# Sheet2.net
KiCad netlist of a schematic drawn in Altium Designer
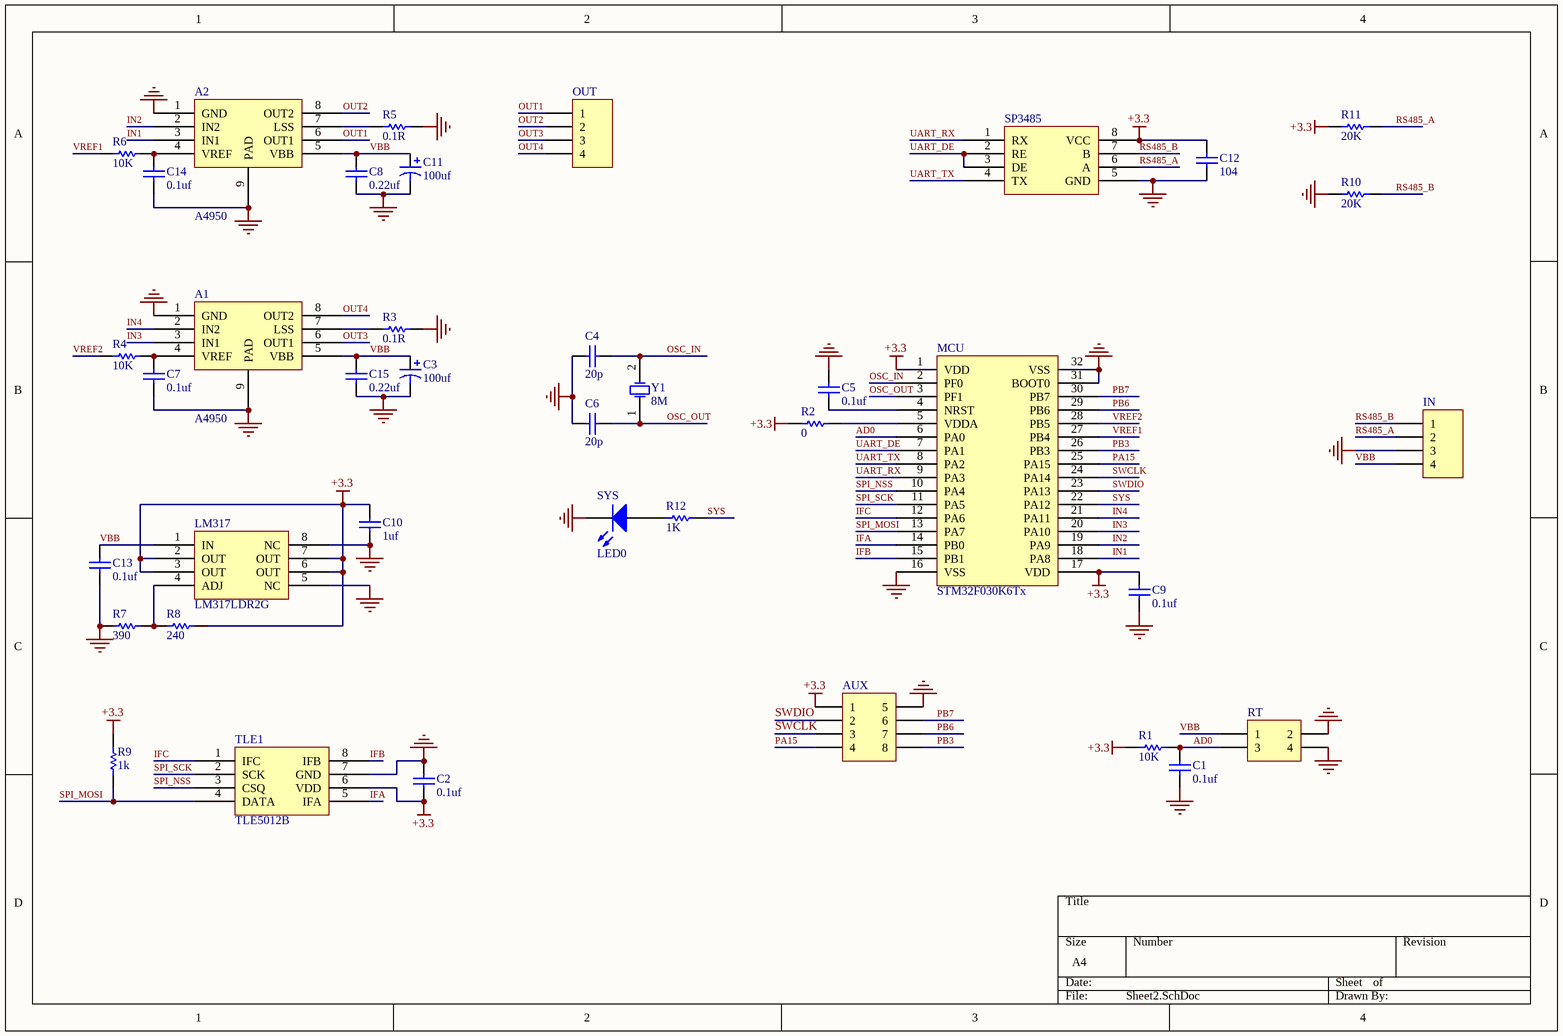
[diagram p0: Sheet2.SchDoc]

(export (version "E")
  (design (tool "Eeschema 10.0.6"))
  (components
    (comp (ref "A1") (value "A4950") (footprint "SOIC-8P") (libsource (lib "Schlib1") (part "A4950")))
    (comp (ref "A2") (value "A4950") (footprint "SOIC-8P") (libsource (lib "Schlib1") (part "A4950")))
    (comp (ref "AUX")
      (value "Header 4X2A")
      (footprint "HDR2X4")
      (description "Header, 4-Pin, Dual row")
      (fields (field (name "PUBLISHER") "Altium Limited"))
      (libsource (lib "Miscellaneous Connectors") (part "Header 4X2A"))
    )
    (comp (ref "C1")
      (value "0.1uf")
      (footprint "0603")
      (description "Capacitor")
      (fields (field (name "Comment") "Cap") (field (name "PUBLISHER") "Altium Limited"))
      (libsource (lib "Miscellaneous Devices") (part "Cap"))
    )
    (comp (ref "C2")
      (value "0.1uf")
      (footprint "0603")
      (description "Capacitor")
      (fields (field (name "Comment") "Cap") (field (name "PUBLISHER") "Altium Limited"))
      (libsource (lib "Miscellaneous Devices") (part "Cap"))
    )
    (comp (ref "C3")
      (value "100uf")
      (footprint "RB.1/.2-F")
      (description "Polarized Capacitor (Radial)")
      (fields (field (name "Comment") "Cap Pol1") (field (name "PUBLISHER") "Altium Limited"))
      (libsource (lib "Miscellaneous Devices") (part "Cap Pol1"))
    )
    (comp (ref "C4")
      (value "20p")
      (footprint "0603")
      (description "Capacitor")
      (fields (field (name "Comment") "Cap") (field (name "PUBLISHER") "Altium Limited"))
      (libsource (lib "Miscellaneous Devices") (part "Cap"))
    )
    (comp (ref "C5")
      (value "0.1uf")
      (footprint "0603")
      (description "Capacitor")
      (fields (field (name "Comment") "Cap") (field (name "PUBLISHER") "Altium Limited"))
      (libsource (lib "Miscellaneous Devices") (part "Cap"))
    )
    (comp (ref "C6")
      (value "20p")
      (footprint "0603")
      (description "Capacitor")
      (fields (field (name "Comment") "Cap") (field (name "PUBLISHER") "Altium Limited"))
      (libsource (lib "Miscellaneous Devices") (part "Cap"))
    )
    (comp (ref "C7")
      (value "0.1uf")
      (footprint "0603")
      (description "Capacitor")
      (fields (field (name "Comment") "Cap") (field (name "PUBLISHER") "Altium Limited"))
      (libsource (lib "Miscellaneous Devices") (part "Cap"))
    )
    (comp (ref "C8")
      (value "0.22uf")
      (footprint "0603")
      (description "Capacitor")
      (fields (field (name "Comment") "Cap") (field (name "PUBLISHER") "Altium Limited"))
      (libsource (lib "Miscellaneous Devices") (part "Cap"))
    )
    (comp (ref "C9")
      (value "0.1uf")
      (footprint "0603")
      (description "Capacitor")
      (fields (field (name "Comment") "Cap") (field (name "PUBLISHER") "Altium Limited"))
      (libsource (lib "Miscellaneous Devices") (part "Cap"))
    )
    (comp (ref "C10")
      (value "1uf")
      (footprint "0603")
      (description "Capacitor")
      (fields (field (name "Comment") "Cap") (field (name "PUBLISHER") "Altium Limited"))
      (libsource (lib "Miscellaneous Devices") (part "Cap"))
    )
    (comp (ref "C11")
      (value "100uf")
      (footprint "RB.1/.2-F")
      (description "Polarized Capacitor (Radial)")
      (fields (field (name "Comment") "Cap Pol1") (field (name "PUBLISHER") "Altium Limited"))
      (libsource (lib "Miscellaneous Devices") (part "Cap Pol1"))
    )
    (comp (ref "C12")
      (value "104")
      (footprint "0603")
      (description "Capacitor")
      (fields (field (name "Comment") "Cap") (field (name "PUBLISHER") "Altium Limited"))
      (libsource (lib "Miscellaneous Devices") (part "Cap"))
    )
    (comp (ref "C13")
      (value "0.1uf")
      (footprint "0603")
      (description "Capacitor")
      (fields (field (name "Comment") "Cap") (field (name "PUBLISHER") "Altium Limited"))
      (libsource (lib "Miscellaneous Devices") (part "Cap"))
    )
    (comp (ref "C14")
      (value "0.1uf")
      (footprint "0603")
      (description "Capacitor")
      (fields (field (name "Comment") "Cap") (field (name "PUBLISHER") "Altium Limited"))
      (libsource (lib "Miscellaneous Devices") (part "Cap"))
    )
    (comp (ref "C15")
      (value "0.22uf")
      (footprint "0603")
      (description "Capacitor")
      (fields (field (name "Comment") "Cap") (field (name "PUBLISHER") "Altium Limited"))
      (libsource (lib "Miscellaneous Devices") (part "Cap"))
    )
    (comp (ref "IN")
      (value "Header 4")
      (footprint "KF2EDG3.81-4P")
      (description "Header, 4-Pin")
      (fields (field (name "PUBLISHER") "Altium Limited"))
      (libsource (lib "Miscellaneous Connectors") (part "Header 4"))
    )
    (comp (ref "LM317")
      (value "LM317LDR2G")
      (footprint "SOIC-8")
      (libsource (lib "Schlib1") (part "LM317LDR2G"))
    )
    (comp (ref "MCU")
      (value "STM32F030K6Tx")
      (footprint "LQFP-32")
      (libsource (lib "Schlib1") (part "STM32F030K6Tx"))
    )
    (comp (ref "OUT")
      (value "Header 4")
      (footprint "HDR4X1-2.54-R")
      (description "Header, 4-Pin")
      (fields (field (name "PUBLISHER") "Altium Limited"))
      (libsource (lib "Miscellaneous Connectors") (part "Header 4"))
    )
    (comp (ref "R1")
      (value "10K")
      (footprint "0603")
      (description "Resistor")
      (fields (field (name "Comment") "Res1") (field (name "PUBLISHER") "Altium Limited"))
      (libsource (lib "Miscellaneous Devices") (part "Res1"))
    )
    (comp (ref "R2")
      (value "0")
      (footprint "0603")
      (description "Resistor")
      (fields (field (name "Comment") "Res1") (field (name "PUBLISHER") "Altium Limited"))
      (libsource (lib "Miscellaneous Devices") (part "Res1"))
    )
    (comp (ref "R3")
      (value "0.1R")
      (footprint "1206")
      (description "Resistor")
      (fields (field (name "Comment") "Res1") (field (name "PUBLISHER") "Altium Limited"))
      (libsource (lib "Miscellaneous Devices") (part "Res1"))
    )
    (comp (ref "R4")
      (value "10K")
      (footprint "0603")
      (description "Resistor")
      (fields (field (name "Comment") "Res1") (field (name "PUBLISHER") "Altium Limited"))
      (libsource (lib "Miscellaneous Devices") (part "Res1"))
    )
    (comp (ref "R5")
      (value "0.1R")
      (footprint "1206")
      (description "Resistor")
      (fields (field (name "Comment") "Res1") (field (name "PUBLISHER") "Altium Limited"))
      (libsource (lib "Miscellaneous Devices") (part "Res1"))
    )
    (comp (ref "R6")
      (value "10K")
      (footprint "0603")
      (description "Resistor")
      (fields (field (name "Comment") "Res1") (field (name "PUBLISHER") "Altium Limited"))
      (libsource (lib "Miscellaneous Devices") (part "Res1"))
    )
    (comp (ref "R7")
      (value "390")
      (footprint "0603")
      (description "Resistor")
      (fields (field (name "Comment") "Res1") (field (name "PUBLISHER") "Altium Limited"))
      (libsource (lib "Miscellaneous Devices") (part "Res1"))
    )
    (comp (ref "R8")
      (value "240")
      (footprint "0603")
      (description "Resistor")
      (fields (field (name "Comment") "Res1") (field (name "PUBLISHER") "Altium Limited"))
      (libsource (lib "Miscellaneous Devices") (part "Res1"))
    )
    (comp (ref "R9")
      (value "1k")
      (footprint "0603")
      (description "Resistor")
      (fields (field (name "Comment") "Res1") (field (name "PUBLISHER") "Altium Limited"))
      (libsource (lib "Miscellaneous Devices") (part "Res1"))
    )
    (comp (ref "R10")
      (value "20K")
      (footprint "0603")
      (description "Resistor")
      (fields (field (name "Comment") "Res1") (field (name "PUBLISHER") "Altium Limited"))
      (libsource (lib "Miscellaneous Devices") (part "Res1"))
    )
    (comp (ref "R11")
      (value "20K")
      (footprint "0603")
      (description "Resistor")
      (fields (field (name "Comment") "Res1") (field (name "PUBLISHER") "Altium Limited"))
      (libsource (lib "Miscellaneous Devices") (part "Res1"))
    )
    (comp (ref "R12")
      (value "1K")
      (footprint "0603")
      (description "Resistor")
      (fields (field (name "Comment") "Res1") (field (name "PUBLISHER") "Altium Limited"))
      (libsource (lib "Miscellaneous Devices") (part "Res1"))
    )
    (comp (ref "RT")
      (value "Header 2X2")
      (footprint "HDR2X2")
      (description "Header, 2-Pin, Dual row")
      (fields (field (name "PUBLISHER") "Altium Limited"))
      (libsource (lib "Miscellaneous Connectors") (part "Header 2X2"))
    )
    (comp (ref "SP3485") (value "SP3485") (footprint "SOIC-8") (libsource (lib "Schlib1") (part "SP3485")))
    (comp (ref "SYS")
      (value "LED0")
      (footprint "0603")
      (description "Typical INFRARED GaAs LED")
      (fields (field (name "PUBLISHER") "Altium Limited"))
      (libsource (lib "Miscellaneous Devices") (part "LED0"))
    )
    (comp (ref "TLE1") (value "TLE5012B") (footprint "SOIC-8") (libsource (lib "Schlib1") (part "TLE5012B")))
    (comp (ref "Y1")
      (value "8M")
      (footprint "XTAL-1")
      (description "Crystal Oscillator")
      (fields (field (name "PUBLISHER") "Altium Limited"))
      (libsource (lib "Miscellaneous Devices") (part "XTAL"))
    )
  )
  (nets
    (net (code "1") (name "+3.3") (class "Default")
      (node (ref "AUX") (pin "1") (pinfunction "1_1") (pintype "passive"))
      (node (ref "C10") (pin "2") (pinfunction "2_2") (pintype "passive"))
      (node (ref "C12") (pin "2") (pinfunction "2_2") (pintype "passive"))
      (node (ref "C2") (pin "1") (pinfunction "1_1") (pintype "passive"))
      (node (ref "C9") (pin "2") (pinfunction "2_2") (pintype "passive"))
      (node (ref "LM317") (pin "2") (pinfunction "OUT_2") (pintype "passive"))
      (node (ref "LM317") (pin "3") (pinfunction "OUT_3") (pintype "passive"))
      (node (ref "LM317") (pin "6") (pinfunction "OUT_6") (pintype "passive"))
      (node (ref "LM317") (pin "7") (pinfunction "OUT_7") (pintype "passive"))
      (node (ref "MCU") (pin "1") (pinfunction "VDD_1") (pintype "passive"))
      (node (ref "MCU") (pin "17") (pinfunction "VDD_17") (pintype "passive"))
      (node (ref "R1") (pin "1") (pinfunction "1_1") (pintype "passive"))
      (node (ref "R11") (pin "1") (pinfunction "1_1") (pintype "passive"))
      (node (ref "R2") (pin "2") (pinfunction "2_2") (pintype "passive"))
      (node (ref "R8") (pin "1") (pinfunction "1_1") (pintype "passive"))
      (node (ref "R9") (pin "1") (pinfunction "1_1") (pintype "passive"))
      (node (ref "SP3485") (pin "8") (pinfunction "VCC_8") (pintype "passive"))
      (node (ref "TLE1") (pin "6") (pinfunction "VDD_6") (pintype "passive"))
    )
    (net (code "2") (name "/AD0") (class "Default")
      (node (ref "C1") (pin "1") (pinfunction "1_1") (pintype "passive"))
      (node (ref "MCU") (pin "6") (pinfunction "PA0_6") (pintype "passive"))
      (node (ref "R1") (pin "2") (pinfunction "2_2") (pintype "passive"))
      (node (ref "RT") (pin "3") (pinfunction "3_3") (pintype "passive"))
    )
    (net (code "3") (name "/IFA") (class "Default")
      (node (ref "MCU") (pin "14") (pinfunction "PB0_14") (pintype "passive"))
      (node (ref "TLE1") (pin "5") (pinfunction "IFA_5") (pintype "passive"))
    )
    (net (code "4") (name "/IFB") (class "Default")
      (node (ref "MCU") (pin "15") (pinfunction "PB1_15") (pintype "passive"))
      (node (ref "TLE1") (pin "8") (pinfunction "IFB_8") (pintype "passive"))
    )
    (net (code "5") (name "/IFC") (class "Default")
      (node (ref "MCU") (pin "12") (pinfunction "PA6_12") (pintype "passive"))
      (node (ref "TLE1") (pin "1") (pinfunction "IFC_1") (pintype "passive"))
    )
    (net (code "6") (name "/IN1") (class "Default")
      (node (ref "A2") (pin "3") (pinfunction "IN1_3") (pintype "passive"))
      (node (ref "MCU") (pin "18") (pinfunction "PA8_18") (pintype "passive"))
    )
    (net (code "7") (name "/IN2") (class "Default")
      (node (ref "A2") (pin "2") (pinfunction "IN2_2") (pintype "passive"))
      (node (ref "MCU") (pin "19") (pinfunction "PA9_19") (pintype "passive"))
    )
    (net (code "8") (name "/IN3") (class "Default")
      (node (ref "A1") (pin "3") (pinfunction "IN1_3") (pintype "passive"))
      (node (ref "MCU") (pin "20") (pinfunction "PA10_20") (pintype "passive"))
    )
    (net (code "9") (name "/IN4") (class "Default")
      (node (ref "A1") (pin "2") (pinfunction "IN2_2") (pintype "passive"))
      (node (ref "MCU") (pin "21") (pinfunction "PA11_21") (pintype "passive"))
    )
    (net (code "10") (name "/OSC_IN") (class "Default")
      (node (ref "C4") (pin "1") (pinfunction "1_1") (pintype "passive"))
      (node (ref "MCU") (pin "2") (pinfunction "PF0_2") (pintype "passive"))
      (node (ref "Y1") (pin "2") (pinfunction "OSC2_2") (pintype "passive"))
    )
    (net (code "11") (name "/OSC_OUT") (class "Default")
      (node (ref "C6") (pin "1") (pinfunction "1_1") (pintype "passive"))
      (node (ref "MCU") (pin "3") (pinfunction "PF1_3") (pintype "passive"))
      (node (ref "Y1") (pin "1") (pinfunction "OSC1_1") (pintype "passive"))
    )
    (net (code "12") (name "/OUT1") (class "Default")
      (node (ref "A2") (pin "6") (pinfunction "OUT1_6") (pintype "passive"))
      (node (ref "OUT") (pin "1") (pinfunction "1_1") (pintype "passive"))
    )
    (net (code "13") (name "/OUT2") (class "Default")
      (node (ref "A2") (pin "8") (pinfunction "OUT2_8") (pintype "passive"))
      (node (ref "OUT") (pin "2") (pinfunction "2_2") (pintype "passive"))
    )
    (net (code "14") (name "/OUT3") (class "Default")
      (node (ref "A1") (pin "6") (pinfunction "OUT1_6") (pintype "passive"))
      (node (ref "OUT") (pin "3") (pinfunction "3_3") (pintype "passive"))
    )
    (net (code "15") (name "/OUT4") (class "Default")
      (node (ref "A1") (pin "8") (pinfunction "OUT2_8") (pintype "passive"))
      (node (ref "OUT") (pin "4") (pinfunction "4_4") (pintype "passive"))
    )
    (net (code "16") (name "/PA15") (class "Default")
      (node (ref "AUX") (pin "4") (pinfunction "4_4") (pintype "passive"))
      (node (ref "MCU") (pin "25") (pinfunction "PA15_25") (pintype "passive"))
    )
    (net (code "17") (name "/PB3") (class "Default")
      (node (ref "AUX") (pin "8") (pinfunction "8_8") (pintype "passive"))
      (node (ref "MCU") (pin "26") (pinfunction "PB3_26") (pintype "passive"))
    )
    (net (code "18") (name "/PB6") (class "Default")
      (node (ref "AUX") (pin "7") (pinfunction "7_7") (pintype "passive"))
      (node (ref "MCU") (pin "29") (pinfunction "PB6_29") (pintype "passive"))
    )
    (net (code "19") (name "/PB7") (class "Default")
      (node (ref "AUX") (pin "6") (pinfunction "6_6") (pintype "passive"))
      (node (ref "MCU") (pin "30") (pinfunction "PB7_30") (pintype "passive"))
    )
    (net (code "20") (name "/RS485_A") (class "Default")
      (node (ref "IN") (pin "2") (pinfunction "2_2") (pintype "passive"))
      (node (ref "R11") (pin "2") (pinfunction "2_2") (pintype "passive"))
      (node (ref "SP3485") (pin "6") (pinfunction "A_6") (pintype "passive"))
    )
    (net (code "21") (name "/RS485_B") (class "Default")
      (node (ref "IN") (pin "1") (pinfunction "1_1") (pintype "passive"))
      (node (ref "R10") (pin "2") (pinfunction "2_2") (pintype "passive"))
      (node (ref "SP3485") (pin "7") (pinfunction "B_7") (pintype "passive"))
    )
    (net (code "22") (name "/SPI_MOSI") (class "Default")
      (node (ref "MCU") (pin "13") (pinfunction "PA7_13") (pintype "passive"))
      (node (ref "R9") (pin "2") (pinfunction "2_2") (pintype "passive"))
      (node (ref "TLE1") (pin "4") (pinfunction "DATA_4") (pintype "passive"))
    )
    (net (code "23") (name "/SPI_NSS") (class "Default")
      (node (ref "MCU") (pin "10") (pinfunction "PA4_10") (pintype "passive"))
      (node (ref "TLE1") (pin "3") (pinfunction "CSQ_3") (pintype "passive"))
    )
    (net (code "24") (name "/SPI_SCK") (class "Default")
      (node (ref "MCU") (pin "11") (pinfunction "PA5_11") (pintype "passive"))
      (node (ref "TLE1") (pin "2") (pinfunction "SCK_2") (pintype "passive"))
    )
    (net (code "25") (name "/SWCLK") (class "Default")
      (node (ref "AUX") (pin "3") (pinfunction "3_3") (pintype "passive"))
      (node (ref "MCU") (pin "24") (pinfunction "PA14_24") (pintype "passive"))
    )
    (net (code "26") (name "/SWDIO") (class "Default")
      (node (ref "AUX") (pin "2") (pinfunction "2_2") (pintype "passive"))
      (node (ref "MCU") (pin "23") (pinfunction "PA13_23") (pintype "passive"))
    )
    (net (code "27") (name "/SYS") (class "Default")
      (node (ref "MCU") (pin "22") (pinfunction "PA12_22") (pintype "passive"))
      (node (ref "R12") (pin "1") (pinfunction "1_1") (pintype "passive"))
    )
    (net (code "28") (name "/UART_DE") (class "Default")
      (node (ref "MCU") (pin "7") (pinfunction "PA1_7") (pintype "passive"))
      (node (ref "SP3485") (pin "2") (pinfunction "RE_2") (pintype "passive"))
      (node (ref "SP3485") (pin "3") (pinfunction "DE_3") (pintype "passive"))
    )
    (net (code "29") (name "/UART_RX") (class "Default")
      (node (ref "MCU") (pin "9") (pinfunction "PA3_9") (pintype "passive"))
      (node (ref "SP3485") (pin "1") (pinfunction "RX_1") (pintype "passive"))
    )
    (net (code "30") (name "/UART_TX") (class "Default")
      (node (ref "MCU") (pin "8") (pinfunction "PA2_8") (pintype "passive"))
      (node (ref "SP3485") (pin "4") (pinfunction "TX_4") (pintype "passive"))
    )
    (net (code "31") (name "/VBB") (class "Default")
      (node (ref "A1") (pin "5") (pinfunction "VBB_5") (pintype "passive"))
      (node (ref "A2") (pin "5") (pinfunction "VBB_5") (pintype "passive"))
      (node (ref "C11") (pin "1") (pinfunction "1_1") (pintype "passive"))
      (node (ref "C13") (pin "2") (pinfunction "2_2") (pintype "passive"))
      (node (ref "C15") (pin "2") (pinfunction "2_2") (pintype "passive"))
      (node (ref "C3") (pin "1") (pinfunction "1_1") (pintype "passive"))
      (node (ref "C8") (pin "2") (pinfunction "2_2") (pintype "passive"))
      (node (ref "IN") (pin "4") (pinfunction "4_4") (pintype "passive"))
      (node (ref "LM317") (pin "1") (pinfunction "IN_1") (pintype "passive"))
      (node (ref "RT") (pin "1") (pinfunction "1_1") (pintype "passive"))
    )
    (net (code "32") (name "/VREF1") (class "Default")
      (node (ref "MCU") (pin "27") (pinfunction "PB4_27") (pintype "passive"))
      (node (ref "R6") (pin "2") (pinfunction "2_2") (pintype "passive"))
    )
    (net (code "33") (name "/VREF2") (class "Default")
      (node (ref "MCU") (pin "28") (pinfunction "PB5_28") (pintype "passive"))
      (node (ref "R4") (pin "2") (pinfunction "2_2") (pintype "passive"))
    )
    (net (code "34") (name "GND") (class "Default")
      (node (ref "A1") (pin "1") (pinfunction "GND_1") (pintype "passive"))
      (node (ref "A1") (pin "9") (pinfunction "PAD_9") (pintype "passive"))
      (node (ref "A2") (pin "1") (pinfunction "GND_1") (pintype "passive"))
      (node (ref "A2") (pin "9") (pinfunction "PAD_9") (pintype "passive"))
      (node (ref "AUX") (pin "5") (pinfunction "5_5") (pintype "passive"))
      (node (ref "C1") (pin "2") (pinfunction "2_2") (pintype "passive"))
      (node (ref "C10") (pin "1") (pinfunction "1_1") (pintype "passive"))
      (node (ref "C11") (pin "2") (pinfunction "2_2") (pintype "passive"))
      (node (ref "C12") (pin "1") (pinfunction "1_1") (pintype "passive"))
      (node (ref "C13") (pin "1") (pinfunction "1_1") (pintype "passive"))
      (node (ref "C14") (pin "1") (pinfunction "1_1") (pintype "passive"))
      (node (ref "C15") (pin "1") (pinfunction "1_1") (pintype "passive"))
      (node (ref "C2") (pin "2") (pinfunction "2_2") (pintype "passive"))
      (node (ref "C3") (pin "2") (pinfunction "2_2") (pintype "passive"))
      (node (ref "C4") (pin "2") (pinfunction "2_2") (pintype "passive"))
      (node (ref "C5") (pin "2") (pinfunction "2_2") (pintype "passive"))
      (node (ref "C6") (pin "2") (pinfunction "2_2") (pintype "passive"))
      (node (ref "C7") (pin "1") (pinfunction "1_1") (pintype "passive"))
      (node (ref "C8") (pin "1") (pinfunction "1_1") (pintype "passive"))
      (node (ref "C9") (pin "1") (pinfunction "1_1") (pintype "passive"))
      (node (ref "IN") (pin "3") (pinfunction "3_3") (pintype "passive"))
      (node (ref "LM317") (pin "5") (pinfunction "NC_5") (pintype "passive"))
      (node (ref "LM317") (pin "8") (pinfunction "NC_8") (pintype "passive"))
      (node (ref "MCU") (pin "16") (pinfunction "VSS_16") (pintype "passive"))
      (node (ref "MCU") (pin "31") (pinfunction "BOOT0_31") (pintype "passive"))
      (node (ref "MCU") (pin "32") (pinfunction "VSS_32") (pintype "passive"))
      (node (ref "R10") (pin "1") (pinfunction "1_1") (pintype "passive"))
      (node (ref "R3") (pin "2") (pinfunction "2_2") (pintype "passive"))
      (node (ref "R5") (pin "2") (pinfunction "2_2") (pintype "passive"))
      (node (ref "R7") (pin "2") (pinfunction "2_2") (pintype "passive"))
      (node (ref "RT") (pin "2") (pinfunction "2_2") (pintype "passive"))
      (node (ref "RT") (pin "4") (pinfunction "4_4") (pintype "passive"))
      (node (ref "SP3485") (pin "5") (pinfunction "GND_5") (pintype "passive"))
      (node (ref "SYS") (pin "2") (pinfunction "K_2") (pintype "passive"))
      (node (ref "TLE1") (pin "7") (pinfunction "GND_7") (pintype "passive"))
    )
    (net (code "35") (name "Net-(A1-LSS)") (class "Default")
      (node (ref "A1") (pin "7") (pinfunction "LSS_7") (pintype "passive"))
      (node (ref "R3") (pin "1") (pinfunction "1_1") (pintype "passive"))
    )
    (net (code "36") (name "Net-(A1-VREF)") (class "Default")
      (node (ref "A1") (pin "4") (pinfunction "VREF_4") (pintype "passive"))
      (node (ref "C7") (pin "2") (pinfunction "2_2") (pintype "passive"))
      (node (ref "R4") (pin "1") (pinfunction "1_1") (pintype "passive"))
    )
    (net (code "37") (name "Net-(A2-LSS)") (class "Default")
      (node (ref "A2") (pin "7") (pinfunction "LSS_7") (pintype "passive"))
      (node (ref "R5") (pin "1") (pinfunction "1_1") (pintype "passive"))
    )
    (net (code "38") (name "Net-(A2-VREF)") (class "Default")
      (node (ref "A2") (pin "4") (pinfunction "VREF_4") (pintype "passive"))
      (node (ref "C14") (pin "2") (pinfunction "2_2") (pintype "passive"))
      (node (ref "R6") (pin "1") (pinfunction "1_1") (pintype "passive"))
    )
    (net (code "39") (name "Net-(LM317-ADJ)") (class "Default")
      (node (ref "LM317") (pin "4") (pinfunction "ADJ_4") (pintype "passive"))
      (node (ref "R7") (pin "1") (pinfunction "1_1") (pintype "passive"))
      (node (ref "R8") (pin "2") (pinfunction "2_2") (pintype "passive"))
    )
    (net (code "40") (name "Net-(MCU-NRST)") (class "Default")
      (node (ref "C5") (pin "1") (pinfunction "1_1") (pintype "passive"))
      (node (ref "MCU") (pin "4") (pinfunction "NRST_4") (pintype "passive"))
    )
    (net (code "41") (name "Net-(MCU-VDDA)") (class "Default")
      (node (ref "MCU") (pin "5") (pinfunction "VDDA_5") (pintype "passive"))
      (node (ref "R2") (pin "1") (pinfunction "1_1") (pintype "passive"))
    )
    (net (code "42") (name "Net-(SYS-A)") (class "Default")
      (node (ref "R12") (pin "2") (pinfunction "2_2") (pintype "passive"))
      (node (ref "SYS") (pin "1") (pinfunction "A_1") (pintype "passive"))
    )
  )
)
